# iomodul.net
KiCad netlist of a schematic drawn in EAGLE
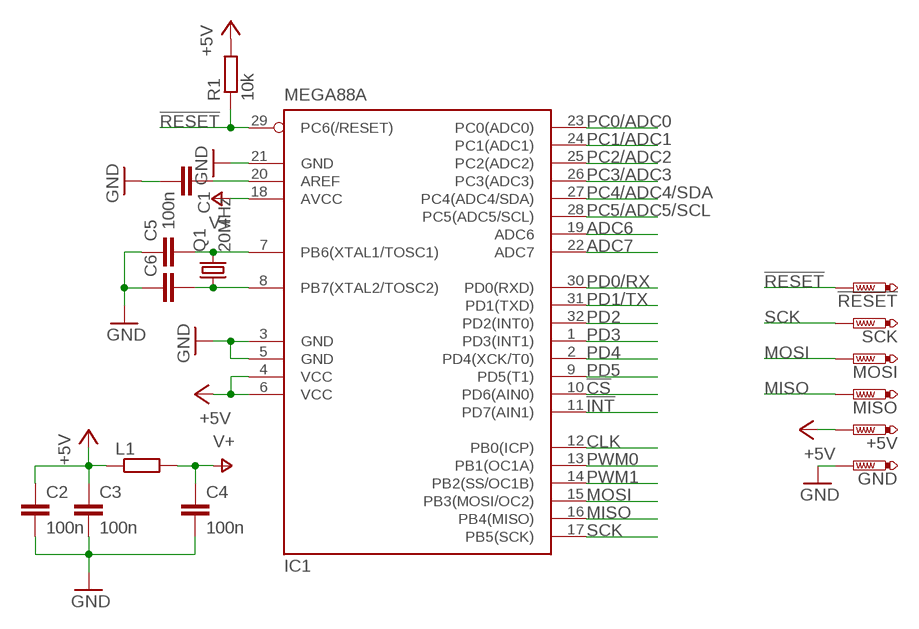
[diagram p0: schematic, sheet 1]
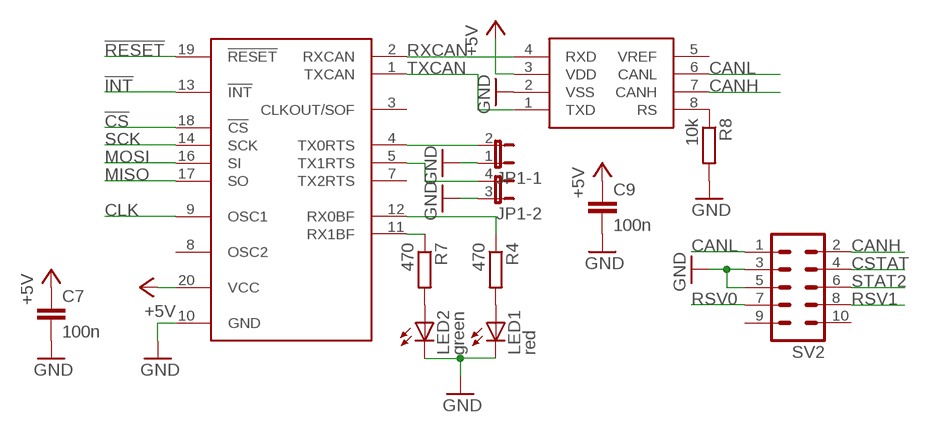
[diagram p1: schematic, sheet 2]
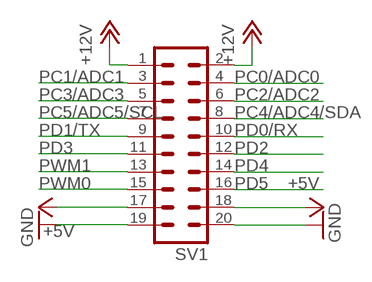
[diagram p2: schematic, sheet 3]
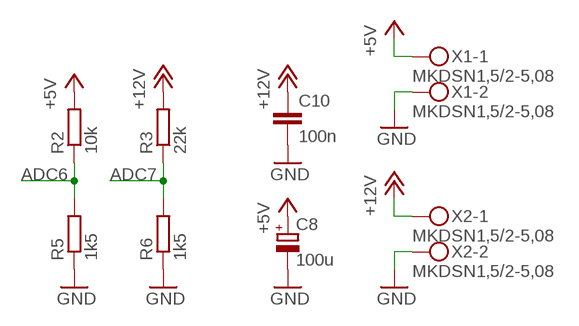
[diagram p3: schematic, sheet 4]

(export (version "E")
  (design (tool "Eeschema 10.0.6"))
  (components
    (comp (ref "!RESET")
      (value "PTR1TP12R")
      (footprint "eagle-import:TP12R")
      (libsource (lib "eagle-import") (part "PTR1TP12R"))
    )
    (comp (ref "+5V")
      (value "PTR1TP12R")
      (footprint "eagle-import:TP12R")
      (libsource (lib "eagle-import") (part "PTR1TP12R"))
    )
    (comp (ref "C1")
      (value "100n")
      (footprint "eagle-import:C0805")
      (libsource (lib "eagle-import") (part "C-EUC0805"))
    )
    (comp (ref "C2")
      (value "100n")
      (footprint "eagle-import:C0805")
      (libsource (lib "eagle-import") (part "C-EUC0805"))
    )
    (comp (ref "C3")
      (value "100n")
      (footprint "eagle-import:C0805")
      (libsource (lib "eagle-import") (part "C-EUC0805"))
    )
    (comp (ref "C4")
      (value "100n")
      (footprint "eagle-import:C0805")
      (libsource (lib "eagle-import") (part "C-EUC0805"))
    )
    (comp (ref "C5")
      (value "C-EUC0805")
      (footprint "eagle-import:C0805")
      (libsource (lib "eagle-import") (part "C-EUC0805"))
    )
    (comp (ref "C6")
      (value "C-EUC0805")
      (footprint "eagle-import:C0805")
      (libsource (lib "eagle-import") (part "C-EUC0805"))
    )
    (comp (ref "GND")
      (value "PTR1TP12R")
      (footprint "eagle-import:TP12R")
      (libsource (lib "eagle-import") (part "PTR1TP12R"))
    )
    (comp (ref "IC1")
      (value "MEGA88A")
      (footprint "eagle-import:TQFP32-08")
      (fields (field (name "MPN") "ATMEGA8-16AU"))
      (libsource (lib "eagle-import") (part "MEGA8-AI"))
    )
    (comp (ref "L1")
      (value "R-EU_R0805")
      (footprint "eagle-import:R0805")
      (libsource (lib "eagle-import") (part "R-EU_R0805"))
    )
    (comp (ref "MISO")
      (value "PTR1TP12R")
      (footprint "eagle-import:TP12R")
      (libsource (lib "eagle-import") (part "PTR1TP12R"))
    )
    (comp (ref "MOSI")
      (value "PTR1TP12R")
      (footprint "eagle-import:TP12R")
      (libsource (lib "eagle-import") (part "PTR1TP12R"))
    )
    (comp (ref "Q1")
      (value "20MHz")
      (footprint "eagle-import:HC49_S")
      (libsource (lib "eagle-import") (part "CRYSTALHC49S"))
    )
    (comp (ref "R1")
      (value "10k")
      (footprint "eagle-import:R0805")
      (libsource (lib "eagle-import") (part "R-EU_R0805"))
    )
    (comp (ref "SCK")
      (value "PTR1TP12R")
      (footprint "eagle-import:TP12R")
      (libsource (lib "eagle-import") (part "PTR1TP12R"))
    )
    (comp (ref "SV1")
      (value "MA10-2")
      (footprint "eagle-import:MA10-2")
      (libsource (lib "eagle-import") (part "MA10-2"))
    )
    (comp (ref "C8")
      (value "100u")
      (footprint "eagle-import:E2,5-6")
      (libsource (lib "eagle-import") (part "CPOL-EUE2.5-6"))
    )
    (comp (ref "C10")
      (value "100n")
      (footprint "eagle-import:C0805")
      (libsource (lib "eagle-import") (part "C-EUC0805"))
    )
    (comp (ref "R2")
      (value "10k")
      (footprint "eagle-import:R0805")
      (libsource (lib "eagle-import") (part "R-EU_R0805"))
    )
    (comp (ref "R3")
      (value "22k")
      (footprint "eagle-import:R0805")
      (libsource (lib "eagle-import") (part "R-EU_R0805"))
    )
    (comp (ref "R5")
      (value "1k5")
      (footprint "eagle-import:R0805")
      (libsource (lib "eagle-import") (part "R-EU_R0805"))
    )
    (comp (ref "R6")
      (value "1k5")
      (footprint "eagle-import:R0805")
      (libsource (lib "eagle-import") (part "R-EU_R0805"))
    )
    (comp (ref "X1")
      (value "MKDSN1,5/2-5,08")
      (footprint "eagle-import:MKDSN1,5_2-5,08")
      (fields (field (name "MPN") "MKDSN 1,5/2-5.08"))
      (libsource (lib "eagle-import") (part "MKDSN1,5/2-5,08"))
    )
    (comp (ref "X2")
      (value "MKDSN1,5/2-5,08")
      (footprint "eagle-import:MKDSN1,5_2-5,08")
      (fields (field (name "MPN") "MKDSN 1,5/2-5.08"))
      (libsource (lib "eagle-import") (part "MKDSN1,5/2-5,08"))
    )
    (comp (ref "C7")
      (value "100n")
      (footprint "eagle-import:C0805")
      (libsource (lib "eagle-import") (part "C-EUC0805"))
    )
    (comp (ref "C9")
      (value "100n")
      (footprint "eagle-import:C0805")
      (libsource (lib "eagle-import") (part "C-EUC0805"))
    )
    (comp (ref "JP1")
      (value "JP2QE")
      (footprint "eagle-import:JP2Q")
      (libsource (lib "eagle-import") (part "JP2QE"))
    )
    (comp (ref "LED1")
      (value "red")
      (footprint "eagle-import:CHIP-LED0805")
      (libsource (lib "eagle-import") (part "LEDCHIP-LED0805"))
    )
    (comp (ref "LED2")
      (value "green")
      (footprint "eagle-import:CHIP-LED0805")
      (libsource (lib "eagle-import") (part "LEDCHIP-LED0805"))
    )
    (comp (ref "R4")
      (value "470")
      (footprint "eagle-import:R0805")
      (libsource (lib "eagle-import") (part "R-EU_R0805"))
    )
    (comp (ref "R7")
      (value "470")
      (footprint "eagle-import:R0805")
      (libsource (lib "eagle-import") (part "R-EU_R0805"))
    )
    (comp (ref "R8")
      (value "10k")
      (footprint "eagle-import:R0805")
      (libsource (lib "eagle-import") (part "R-EU_R0805"))
    )
    (comp (ref "SV2")
      (value "MA05-2")
      (footprint "eagle-import:MA05-2")
      (libsource (lib "eagle-import") (part "MA05-2"))
    )
    (comp (ref "U$1")
      (value "MCP2515")
      (footprint "eagle-import:TSSOP20")
      (libsource (lib "eagle-import") (part "MCP2515"))
    )
    (comp (ref "U$2")
      (value "MCP2551")
      (footprint "eagle-import:SO-08")
      (libsource (lib "eagle-import") (part "MCP2551"))
    )
  )
  (nets
    (net (code "1") (name "+5V") (class "Default")
      (node (ref "+5V") (pin "TP") (pinfunction "TP_TP") (pintype "input"))
      (node (ref "C2") (pin "1") (pinfunction "1_1") (pintype "passive"))
      (node (ref "C3") (pin "1") (pinfunction "1_1") (pintype "passive"))
      (node (ref "C7") (pin "1") (pinfunction "1_1") (pintype "passive"))
      (node (ref "C8") (pin "+") (pinfunction "+_+") (pintype "passive"))
      (node (ref "C9") (pin "1") (pinfunction "1_1") (pintype "passive"))
      (node (ref "IC1") (pin "4") (pinfunction "VCC_4") (pintype "power_in"))
      (node (ref "IC1") (pin "6") (pinfunction "VCC_6") (pintype "power_in"))
      (node (ref "L1") (pin "1") (pinfunction "1_1") (pintype "passive"))
      (node (ref "R1") (pin "2") (pinfunction "2_2") (pintype "passive"))
      (node (ref "R2") (pin "2") (pinfunction "2_2") (pintype "passive"))
      (node (ref "SV1") (pin "17") (pinfunction "17_17") (pintype "passive"))
      (node (ref "SV1") (pin "18") (pinfunction "18_18") (pintype "passive"))
      (node (ref "U$1") (pin "20") (pinfunction "VCC_20") (pintype "bidirectional"))
      (node (ref "U$2") (pin "3") (pinfunction "VDD_3") (pintype "bidirectional"))
      (node (ref "X1") (pin "1") (pinfunction "KL_1") (pintype "passive"))
    )
    (net (code "2") (name "+12V") (class "Default")
      (node (ref "C10") (pin "1") (pinfunction "1_1") (pintype "passive"))
      (node (ref "R3") (pin "2") (pinfunction "2_2") (pintype "passive"))
      (node (ref "SV1") (pin "1") (pinfunction "1_1") (pintype "passive"))
      (node (ref "SV1") (pin "2") (pinfunction "2_2") (pintype "passive"))
      (node (ref "X2") (pin "1") (pinfunction "KL_1") (pintype "passive"))
    )
    (net (code "3") (name "ADC6") (class "Default")
      (node (ref "IC1") (pin "19") (pinfunction "ADC6_19") (pintype "bidirectional"))
      (node (ref "R2") (pin "1") (pinfunction "1_1") (pintype "passive"))
      (node (ref "R5") (pin "2") (pinfunction "2_2") (pintype "passive"))
    )
    (net (code "4") (name "ADC7") (class "Default")
      (node (ref "IC1") (pin "22") (pinfunction "ADC7_22") (pintype "bidirectional"))
      (node (ref "R3") (pin "1") (pinfunction "1_1") (pintype "passive"))
      (node (ref "R6") (pin "2") (pinfunction "2_2") (pintype "passive"))
    )
    (net (code "5") (name "CANH") (class "Default")
      (node (ref "SV2") (pin "2") (pinfunction "2_2") (pintype "passive"))
      (node (ref "U$2") (pin "7") (pinfunction "CANH_7") (pintype "bidirectional"))
    )
    (net (code "6") (name "CANL") (class "Default")
      (node (ref "SV2") (pin "1") (pinfunction "1_1") (pintype "passive"))
      (node (ref "U$2") (pin "6") (pinfunction "CANL_6") (pintype "bidirectional"))
    )
    (net (code "7") (name "CLK") (class "Default")
      (node (ref "IC1") (pin "12") (pinfunction "PB0(ICP)_12") (pintype "bidirectional"))
      (node (ref "U$1") (pin "9") (pinfunction "OSC1_9") (pintype "bidirectional"))
    )
    (net (code "8") (name "CSTAT") (class "Default")
      (node (ref "SV2") (pin "4") (pinfunction "4_4") (pintype "passive"))
    )
    (net (code "9") (name "GND") (class "Default")
      (node (ref "C1") (pin "2") (pinfunction "2_2") (pintype "passive"))
      (node (ref "C10") (pin "2") (pinfunction "2_2") (pintype "passive"))
      (node (ref "C2") (pin "2") (pinfunction "2_2") (pintype "passive"))
      (node (ref "C3") (pin "2") (pinfunction "2_2") (pintype "passive"))
      (node (ref "C4") (pin "2") (pinfunction "2_2") (pintype "passive"))
      (node (ref "C5") (pin "1") (pinfunction "1_1") (pintype "passive"))
      (node (ref "C6") (pin "1") (pinfunction "1_1") (pintype "passive"))
      (node (ref "C7") (pin "2") (pinfunction "2_2") (pintype "passive"))
      (node (ref "C8") (pin "-") (pinfunction "-_-") (pintype "passive"))
      (node (ref "C9") (pin "2") (pinfunction "2_2") (pintype "passive"))
      (node (ref "GND") (pin "TP") (pinfunction "TP_TP") (pintype "input"))
      (node (ref "IC1") (pin "21") (pinfunction "GND_21") (pintype "power_in"))
      (node (ref "IC1") (pin "3") (pinfunction "GND_3") (pintype "power_in"))
      (node (ref "IC1") (pin "5") (pinfunction "GND_5") (pintype "power_in"))
      (node (ref "JP1") (pin "1") (pinfunction "1_1") (pintype "passive"))
      (node (ref "JP1") (pin "3") (pinfunction "1_3") (pintype "passive"))
      (node (ref "LED1") (pin "C") (pinfunction "C_C") (pintype "passive"))
      (node (ref "LED2") (pin "C") (pinfunction "C_C") (pintype "passive"))
      (node (ref "R5") (pin "1") (pinfunction "1_1") (pintype "passive"))
      (node (ref "R6") (pin "1") (pinfunction "1_1") (pintype "passive"))
      (node (ref "R8") (pin "2") (pinfunction "2_2") (pintype "passive"))
      (node (ref "SV1") (pin "19") (pinfunction "19_19") (pintype "passive"))
      (node (ref "SV1") (pin "20") (pinfunction "20_20") (pintype "passive"))
      (node (ref "SV2") (pin "3") (pinfunction "3_3") (pintype "passive"))
      (node (ref "SV2") (pin "5") (pinfunction "5_5") (pintype "passive"))
      (node (ref "U$1") (pin "10") (pinfunction "GND_10") (pintype "bidirectional"))
      (node (ref "U$2") (pin "2") (pinfunction "VSS_2") (pintype "bidirectional"))
      (node (ref "X1") (pin "2") (pinfunction "KL_2") (pintype "passive"))
      (node (ref "X2") (pin "2") (pinfunction "KL_2") (pintype "passive"))
    )
    (net (code "10") (name "MISO") (class "Default")
      (node (ref "IC1") (pin "16") (pinfunction "PB4(MISO)_16") (pintype "bidirectional"))
      (node (ref "MISO") (pin "TP") (pinfunction "TP_TP") (pintype "input"))
      (node (ref "U$1") (pin "17") (pinfunction "SO_17") (pintype "bidirectional"))
    )
    (net (code "11") (name "MOSI") (class "Default")
      (node (ref "IC1") (pin "15") (pinfunction "PB3(MOSI/OC2)_15") (pintype "bidirectional"))
      (node (ref "MOSI") (pin "TP") (pinfunction "TP_TP") (pintype "input"))
      (node (ref "U$1") (pin "16") (pinfunction "SI_16") (pintype "bidirectional"))
    )
    (net (code "12") (name "Net-(IC1-AREF)") (class "Default")
      (node (ref "C1") (pin "1") (pinfunction "1_1") (pintype "passive"))
      (node (ref "IC1") (pin "20") (pinfunction "AREF_20") (pintype "passive"))
    )
    (net (code "13") (name "Net-(IC1-PB6(XTAL1{slash}TOSC1))") (class "Default")
      (node (ref "C5") (pin "2") (pinfunction "2_2") (pintype "passive"))
      (node (ref "IC1") (pin "7") (pinfunction "PB6(XTAL1/TOSC1)_7") (pintype "bidirectional"))
      (node (ref "Q1") (pin "2") (pinfunction "2_2") (pintype "passive"))
    )
    (net (code "14") (name "Net-(IC1-PB7(XTAL2{slash}TOSC2))") (class "Default")
      (node (ref "C6") (pin "2") (pinfunction "2_2") (pintype "passive"))
      (node (ref "IC1") (pin "8") (pinfunction "PB7(XTAL2/TOSC2)_8") (pintype "bidirectional"))
      (node (ref "Q1") (pin "1") (pinfunction "1_1") (pintype "passive"))
    )
    (net (code "15") (name "Net-(JP1B-2)") (class "Default")
      (node (ref "JP1") (pin "4") (pinfunction "2_4") (pintype "passive"))
      (node (ref "U$1") (pin "5") (pinfunction "TX1RTS_5") (pintype "bidirectional"))
    )
    (net (code "16") (name "Net-(LED1-PadA)") (class "Default")
      (node (ref "LED1") (pin "A") (pinfunction "A_A") (pintype "passive"))
      (node (ref "R4") (pin "2") (pinfunction "2_2") (pintype "passive"))
    )
    (net (code "17") (name "Net-(LED2-PadA)") (class "Default")
      (node (ref "LED2") (pin "A") (pinfunction "A_A") (pintype "passive"))
      (node (ref "R7") (pin "2") (pinfunction "2_2") (pintype "passive"))
    )
    (net (code "18") (name "Net-(U$1-RX0BF)") (class "Default")
      (node (ref "R4") (pin "1") (pinfunction "1_1") (pintype "passive"))
      (node (ref "U$1") (pin "12") (pinfunction "RX0BF_12") (pintype "bidirectional"))
    )
    (net (code "19") (name "Net-(U$1-RX1BF)") (class "Default")
      (node (ref "R7") (pin "1") (pinfunction "1_1") (pintype "passive"))
      (node (ref "U$1") (pin "11") (pinfunction "RX1BF_11") (pintype "bidirectional"))
    )
    (net (code "20") (name "Net-(U$1-TX0RTS)") (class "Default")
      (node (ref "JP1") (pin "2") (pinfunction "2_2") (pintype "passive"))
      (node (ref "U$1") (pin "4") (pinfunction "TX0RTS_4") (pintype "bidirectional"))
    )
    (net (code "21") (name "Net-(U$2-RS)") (class "Default")
      (node (ref "R8") (pin "1") (pinfunction "1_1") (pintype "passive"))
      (node (ref "U$2") (pin "8") (pinfunction "RS_8") (pintype "bidirectional"))
    )
    (net (code "22") (name "PC0{slash}ADC0") (class "Default")
      (node (ref "IC1") (pin "23") (pinfunction "PC0(ADC0)_23") (pintype "bidirectional"))
      (node (ref "SV1") (pin "4") (pinfunction "4_4") (pintype "passive"))
    )
    (net (code "23") (name "PC1{slash}ADC1") (class "Default")
      (node (ref "IC1") (pin "24") (pinfunction "PC1(ADC1)_24") (pintype "bidirectional"))
      (node (ref "SV1") (pin "3") (pinfunction "3_3") (pintype "passive"))
    )
    (net (code "24") (name "PC2{slash}ADC2") (class "Default")
      (node (ref "IC1") (pin "25") (pinfunction "PC2(ADC2)_25") (pintype "bidirectional"))
      (node (ref "SV1") (pin "6") (pinfunction "6_6") (pintype "passive"))
    )
    (net (code "25") (name "PC3{slash}ADC3") (class "Default")
      (node (ref "IC1") (pin "26") (pinfunction "PC3(ADC3)_26") (pintype "bidirectional"))
      (node (ref "SV1") (pin "5") (pinfunction "5_5") (pintype "passive"))
    )
    (net (code "26") (name "PC4{slash}ADC4{slash}SDA") (class "Default")
      (node (ref "IC1") (pin "27") (pinfunction "PC4(ADC4/SDA)_27") (pintype "bidirectional"))
      (node (ref "SV1") (pin "8") (pinfunction "8_8") (pintype "passive"))
    )
    (net (code "27") (name "PC5{slash}ADC5{slash}SCL") (class "Default")
      (node (ref "IC1") (pin "28") (pinfunction "PC5(ADC5/SCL)_28") (pintype "bidirectional"))
      (node (ref "SV1") (pin "7") (pinfunction "7_7") (pintype "passive"))
    )
    (net (code "28") (name "PD0{slash}RX") (class "Default")
      (node (ref "IC1") (pin "30") (pinfunction "PD0(RXD)_30") (pintype "bidirectional"))
      (node (ref "SV1") (pin "10") (pinfunction "10_10") (pintype "passive"))
    )
    (net (code "29") (name "PD1{slash}TX") (class "Default")
      (node (ref "IC1") (pin "31") (pinfunction "PD1(TXD)_31") (pintype "bidirectional"))
      (node (ref "SV1") (pin "9") (pinfunction "9_9") (pintype "passive"))
    )
    (net (code "30") (name "PD2") (class "Default")
      (node (ref "IC1") (pin "32") (pinfunction "PD2(INT0)_32") (pintype "bidirectional"))
      (node (ref "SV1") (pin "12") (pinfunction "12_12") (pintype "passive"))
    )
    (net (code "31") (name "PD3") (class "Default")
      (node (ref "IC1") (pin "1") (pinfunction "PD3(INT1)_1") (pintype "bidirectional"))
      (node (ref "SV1") (pin "11") (pinfunction "11_11") (pintype "passive"))
    )
    (net (code "32") (name "PD4") (class "Default")
      (node (ref "IC1") (pin "2") (pinfunction "PD4(XCK/T0)_2") (pintype "bidirectional"))
      (node (ref "SV1") (pin "14") (pinfunction "14_14") (pintype "passive"))
    )
    (net (code "33") (name "PD5") (class "Default")
      (node (ref "IC1") (pin "9") (pinfunction "PD5(T1)_9") (pintype "bidirectional"))
      (node (ref "SV1") (pin "16") (pinfunction "16_16") (pintype "passive"))
    )
    (net (code "34") (name "PWM0") (class "Default")
      (node (ref "IC1") (pin "13") (pinfunction "PB1(OC1A)_13") (pintype "bidirectional"))
      (node (ref "SV1") (pin "15") (pinfunction "15_15") (pintype "passive"))
    )
    (net (code "35") (name "PWM1") (class "Default")
      (node (ref "IC1") (pin "14") (pinfunction "PB2(SS/OC1B)_14") (pintype "bidirectional"))
      (node (ref "SV1") (pin "13") (pinfunction "13_13") (pintype "passive"))
    )
    (net (code "36") (name "RSV0") (class "Default")
      (node (ref "SV2") (pin "7") (pinfunction "7_7") (pintype "passive"))
    )
    (net (code "37") (name "RSV1") (class "Default")
      (node (ref "SV2") (pin "8") (pinfunction "8_8") (pintype "passive"))
    )
    (net (code "38") (name "RXCAN") (class "Default")
      (node (ref "U$1") (pin "2") (pinfunction "RXCAN_2") (pintype "bidirectional"))
      (node (ref "U$2") (pin "4") (pinfunction "RXD_4") (pintype "bidirectional"))
    )
    (net (code "39") (name "SCK") (class "Default")
      (node (ref "IC1") (pin "17") (pinfunction "PB5(SCK)_17") (pintype "bidirectional"))
      (node (ref "SCK") (pin "TP") (pinfunction "TP_TP") (pintype "input"))
      (node (ref "U$1") (pin "14") (pinfunction "SCK_14") (pintype "bidirectional"))
    )
    (net (code "40") (name "STAT2") (class "Default")
      (node (ref "SV2") (pin "6") (pinfunction "6_6") (pintype "passive"))
    )
    (net (code "41") (name "TXCAN") (class "Default")
      (node (ref "U$1") (pin "1") (pinfunction "TXCAN_1") (pintype "bidirectional"))
      (node (ref "U$2") (pin "1") (pinfunction "TXD_1") (pintype "bidirectional"))
    )
    (net (code "42") (name "V+") (class "Default")
      (node (ref "C4") (pin "1") (pinfunction "1_1") (pintype "passive"))
      (node (ref "IC1") (pin "18") (pinfunction "AVCC_18") (pintype "power_in"))
      (node (ref "L1") (pin "2") (pinfunction "2_2") (pintype "passive"))
    )
    (net (code "43") (name "unconnected-(SV2-Pad9)") (class "Default")
      (node (ref "SV2") (pin "9") (pinfunction "9_9") (pintype "passive"))
    )
    (net (code "44") (name "unconnected-(SV2-Pad10)") (class "Default")
      (node (ref "SV2") (pin "10") (pinfunction "10_10") (pintype "passive"))
    )
    (net (code "45") (name "unconnected-(U$1-CLKOUT{slash}SOF-Pad3)") (class "Default")
      (node (ref "U$1") (pin "3") (pinfunction "CLKOUT/SOF_3") (pintype "bidirectional"))
    )
    (net (code "46") (name "unconnected-(U$1-OSC2-Pad8)") (class "Default")
      (node (ref "U$1") (pin "8") (pinfunction "OSC2_8") (pintype "bidirectional"))
    )
    (net (code "47") (name "unconnected-(U$1-TX2RTS-Pad7)") (class "Default")
      (node (ref "U$1") (pin "7") (pinfunction "TX2RTS_7") (pintype "bidirectional"))
    )
    (net (code "48") (name "unconnected-(U$2-VREF-Pad5)") (class "Default")
      (node (ref "U$2") (pin "5") (pinfunction "VREF_5") (pintype "bidirectional"))
    )
    (net (code "49") (name "~{CS}") (class "Default")
      (node (ref "IC1") (pin "10") (pinfunction "PD6(AIN0)_10") (pintype "bidirectional"))
      (node (ref "U$1") (pin "18") (pinfunction "~{CS}_18") (pintype "bidirectional"))
    )
    (net (code "50") (name "~{INT}") (class "Default")
      (node (ref "IC1") (pin "11") (pinfunction "PD7(AIN1)_11") (pintype "bidirectional"))
      (node (ref "U$1") (pin "13") (pinfunction "~{INT}_13") (pintype "bidirectional"))
    )
    (net (code "51") (name "~{RESET}") (class "Default")
      (node (ref "!RESET") (pin "TP") (pinfunction "TP_TP") (pintype "input"))
      (node (ref "IC1") (pin "29") (pinfunction "PC6(/RESET)_29") (pintype "bidirectional"))
      (node (ref "R1") (pin "1") (pinfunction "1_1") (pintype "passive"))
      (node (ref "U$1") (pin "19") (pinfunction "~{RESET}_19") (pintype "bidirectional"))
    )
  )
)
